# FPGA_Core.net
KiCad netlist of a schematic drawn in Altium Designer
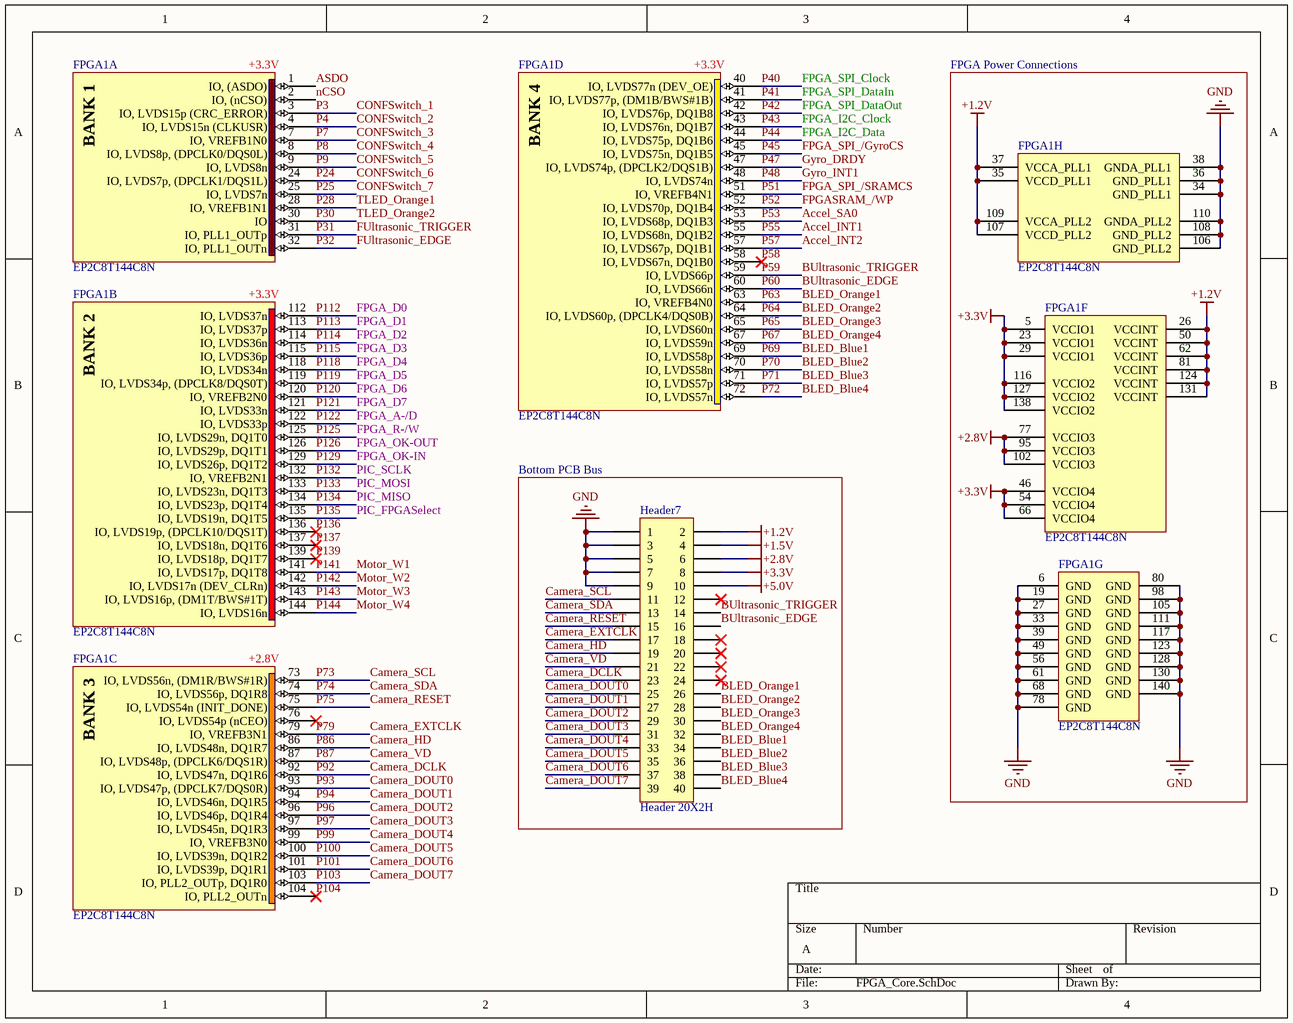
[diagram p0: FPGA_Core.SchDoc]

(export (version "E")
  (design (tool "Eeschema 10.0.6"))
  (components
    (comp (ref "FPGA1")
      (value "EP2C8T144C8N")
      (footprint "TQFP144_N")
      (fields (field (name "PUBLISHER") "Altium Limited"))
      (libsource (lib "Altera Cyclone II") (part "EP2C8T144C8N"))
    )
    (comp (ref "Header7")
      (value "Header 20X2H")
      (footprint "HDR2X20")
      (description "Header, 20-Pin, Dual row, Right Angle")
      (fields (field (name "PUBLISHER") "Altium Limited"))
      (libsource (lib "Miscellaneous Connectors") (part "Header 20X2H"))
    )
  )
  (nets
    (net (code "1") (name "+1.2V") (class "Default")
      (node (ref "FPGA1") (pin "107") (pinfunction "VCCD_PLL2_107") (pintype "power_in"))
      (node (ref "FPGA1") (pin "109") (pinfunction "VCCA_PLL2_109") (pintype "power_in"))
      (node (ref "FPGA1") (pin "124") (pinfunction "VCCINT_124") (pintype "power_in"))
      (node (ref "FPGA1") (pin "131") (pinfunction "VCCINT_131") (pintype "power_in"))
      (node (ref "FPGA1") (pin "26") (pinfunction "VCCINT_26") (pintype "power_in"))
      (node (ref "FPGA1") (pin "35") (pinfunction "VCCD_PLL1_35") (pintype "power_in"))
      (node (ref "FPGA1") (pin "37") (pinfunction "VCCA_PLL1_37") (pintype "power_in"))
      (node (ref "FPGA1") (pin "50") (pinfunction "VCCINT_50") (pintype "power_in"))
      (node (ref "FPGA1") (pin "62") (pinfunction "VCCINT_62") (pintype "power_in"))
      (node (ref "FPGA1") (pin "81") (pinfunction "VCCINT_81") (pintype "power_in"))
      (node (ref "Header7") (pin "2") (pinfunction "2_2") (pintype "passive"))
    )
    (net (code "2") (name "+1.5V") (class "Default")
      (node (ref "Header7") (pin "4") (pinfunction "4_4") (pintype "passive"))
    )
    (net (code "3") (name "+2.8V") (class "Default")
      (node (ref "FPGA1") (pin "102") (pinfunction "VCCIO3_102") (pintype "power_in"))
      (node (ref "FPGA1") (pin "77") (pinfunction "VCCIO3_77") (pintype "power_in"))
      (node (ref "FPGA1") (pin "95") (pinfunction "VCCIO3_95") (pintype "power_in"))
      (node (ref "Header7") (pin "6") (pinfunction "6_6") (pintype "passive"))
    )
    (net (code "4") (name "+3.3V") (class "Default")
      (node (ref "FPGA1") (pin "116") (pinfunction "VCCIO2_116") (pintype "power_in"))
      (node (ref "FPGA1") (pin "127") (pinfunction "VCCIO2_127") (pintype "power_in"))
      (node (ref "FPGA1") (pin "138") (pinfunction "VCCIO2_138") (pintype "power_in"))
      (node (ref "FPGA1") (pin "23") (pinfunction "VCCIO1_23") (pintype "power_in"))
      (node (ref "FPGA1") (pin "29") (pinfunction "VCCIO1_29") (pintype "power_in"))
      (node (ref "FPGA1") (pin "46") (pinfunction "VCCIO4_46") (pintype "power_in"))
      (node (ref "FPGA1") (pin "5") (pinfunction "VCCIO1_5") (pintype "power_in"))
      (node (ref "FPGA1") (pin "54") (pinfunction "VCCIO4_54") (pintype "power_in"))
      (node (ref "FPGA1") (pin "66") (pinfunction "VCCIO4_66") (pintype "power_in"))
      (node (ref "Header7") (pin "8") (pinfunction "8_8") (pintype "passive"))
    )
    (net (code "5") (name "+5.0V") (class "Default")
      (node (ref "Header7") (pin "10") (pinfunction "10_10") (pintype "passive"))
    )
    (net (code "6") (name "/ASDO") (class "Default")
      (node (ref "FPGA1") (pin "1") (pinfunction "IO,_(ASDO)_1") (pintype "bidirectional"))
    )
    (net (code "7") (name "/Accel_INT1") (class "Default")
      (node (ref "FPGA1") (pin "55") (pinfunction "IO,_LVDS68n,_DQ1B2_55") (pintype "bidirectional"))
    )
    (net (code "8") (name "/Accel_INT2") (class "Default")
      (node (ref "FPGA1") (pin "57") (pinfunction "IO,_LVDS67p,_DQ1B1_57") (pintype "bidirectional"))
    )
    (net (code "9") (name "/Accel_SA0") (class "Default")
      (node (ref "FPGA1") (pin "53") (pinfunction "IO,_LVDS68p,_DQ1B3_53") (pintype "bidirectional"))
    )
    (net (code "10") (name "/BLED_Blue1") (class "Default")
      (node (ref "FPGA1") (pin "69") (pinfunction "IO,_LVDS58p_69") (pintype "bidirectional"))
      (node (ref "Header7") (pin "34") (pinfunction "34_34") (pintype "passive"))
    )
    (net (code "11") (name "/BLED_Blue2") (class "Default")
      (node (ref "FPGA1") (pin "70") (pinfunction "IO,_LVDS58n_70") (pintype "bidirectional"))
      (node (ref "Header7") (pin "36") (pinfunction "36_36") (pintype "passive"))
    )
    (net (code "12") (name "/BLED_Blue3") (class "Default")
      (node (ref "FPGA1") (pin "71") (pinfunction "IO,_LVDS57p_71") (pintype "bidirectional"))
      (node (ref "Header7") (pin "38") (pinfunction "38_38") (pintype "passive"))
    )
    (net (code "13") (name "/BLED_Blue4") (class "Default")
      (node (ref "FPGA1") (pin "72") (pinfunction "IO,_LVDS57n_72") (pintype "bidirectional"))
      (node (ref "Header7") (pin "40") (pinfunction "40_40") (pintype "passive"))
    )
    (net (code "14") (name "/BLED_Orange1") (class "Default")
      (node (ref "FPGA1") (pin "63") (pinfunction "IO,_VREFB4N0_63") (pintype "bidirectional"))
      (node (ref "Header7") (pin "26") (pinfunction "26_26") (pintype "passive"))
    )
    (net (code "15") (name "/BLED_Orange2") (class "Default")
      (node (ref "FPGA1") (pin "64") (pinfunction "IO,_LVDS60p,_(DPCLK4/DQS0B)_64") (pintype "bidirectional"))
      (node (ref "Header7") (pin "28") (pinfunction "28_28") (pintype "passive"))
    )
    (net (code "16") (name "/BLED_Orange3") (class "Default")
      (node (ref "FPGA1") (pin "65") (pinfunction "IO,_LVDS60n_65") (pintype "bidirectional"))
      (node (ref "Header7") (pin "30") (pinfunction "30_30") (pintype "passive"))
    )
    (net (code "17") (name "/BLED_Orange4") (class "Default")
      (node (ref "FPGA1") (pin "67") (pinfunction "IO,_LVDS59n_67") (pintype "bidirectional"))
      (node (ref "Header7") (pin "32") (pinfunction "32_32") (pintype "passive"))
    )
    (net (code "18") (name "/BUltrasonic_EDGE") (class "Default")
      (node (ref "FPGA1") (pin "60") (pinfunction "IO,_LVDS66n_60") (pintype "bidirectional"))
      (node (ref "Header7") (pin "16") (pinfunction "16_16") (pintype "passive"))
    )
    (net (code "19") (name "/BUltrasonic_TRIGGER") (class "Default")
      (node (ref "FPGA1") (pin "59") (pinfunction "IO,_LVDS66p_59") (pintype "bidirectional"))
      (node (ref "Header7") (pin "14") (pinfunction "14_14") (pintype "passive"))
    )
    (net (code "20") (name "/CONFSwitch_1") (class "Default")
      (node (ref "FPGA1") (pin "3") (pinfunction "IO,_LVDS15p_(CRC_ERROR)_3") (pintype "bidirectional"))
    )
    (net (code "21") (name "/CONFSwitch_2") (class "Default")
      (node (ref "FPGA1") (pin "4") (pinfunction "IO,_LVDS15n_(CLKUSR)_4") (pintype "bidirectional"))
    )
    (net (code "22") (name "/CONFSwitch_3") (class "Default")
      (node (ref "FPGA1") (pin "7") (pinfunction "IO,_VREFB1N0_7") (pintype "bidirectional"))
    )
    (net (code "23") (name "/CONFSwitch_4") (class "Default")
      (node (ref "FPGA1") (pin "8") (pinfunction "IO,_LVDS8p,_(DPCLK0/DQS0L)_8") (pintype "bidirectional"))
    )
    (net (code "24") (name "/CONFSwitch_5") (class "Default")
      (node (ref "FPGA1") (pin "9") (pinfunction "IO,_LVDS8n_9") (pintype "bidirectional"))
    )
    (net (code "25") (name "/CONFSwitch_6") (class "Default")
      (node (ref "FPGA1") (pin "24") (pinfunction "IO,_LVDS7p,_(DPCLK1/DQS1L)_24") (pintype "bidirectional"))
    )
    (net (code "26") (name "/CONFSwitch_7") (class "Default")
      (node (ref "FPGA1") (pin "25") (pinfunction "IO,_LVDS7n_25") (pintype "bidirectional"))
    )
    (net (code "27") (name "/Camera_DCLK") (class "Default")
      (node (ref "FPGA1") (pin "92") (pinfunction "IO,_LVDS47n,_DQ1R6_92") (pintype "bidirectional"))
      (node (ref "Header7") (pin "23") (pinfunction "23_23") (pintype "passive"))
    )
    (net (code "28") (name "/Camera_DOUT0") (class "Default")
      (node (ref "FPGA1") (pin "93") (pinfunction "IO,_LVDS47p,_(DPCLK7/DQS0R)_93") (pintype "bidirectional"))
      (node (ref "Header7") (pin "25") (pinfunction "25_25") (pintype "passive"))
    )
    (net (code "29") (name "/Camera_DOUT1") (class "Default")
      (node (ref "FPGA1") (pin "94") (pinfunction "IO,_LVDS46n,_DQ1R5_94") (pintype "bidirectional"))
      (node (ref "Header7") (pin "27") (pinfunction "27_27") (pintype "passive"))
    )
    (net (code "30") (name "/Camera_DOUT2") (class "Default")
      (node (ref "FPGA1") (pin "96") (pinfunction "IO,_LVDS46p,_DQ1R4_96") (pintype "bidirectional"))
      (node (ref "Header7") (pin "29") (pinfunction "29_29") (pintype "passive"))
    )
    (net (code "31") (name "/Camera_DOUT3") (class "Default")
      (node (ref "FPGA1") (pin "97") (pinfunction "IO,_LVDS45n,_DQ1R3_97") (pintype "bidirectional"))
      (node (ref "Header7") (pin "31") (pinfunction "31_31") (pintype "passive"))
    )
    (net (code "32") (name "/Camera_DOUT4") (class "Default")
      (node (ref "FPGA1") (pin "99") (pinfunction "IO,_VREFB3N0_99") (pintype "bidirectional"))
      (node (ref "Header7") (pin "33") (pinfunction "33_33") (pintype "passive"))
    )
    (net (code "33") (name "/Camera_DOUT5") (class "Default")
      (node (ref "FPGA1") (pin "100") (pinfunction "IO,_LVDS39n,_DQ1R2_100") (pintype "bidirectional"))
      (node (ref "Header7") (pin "35") (pinfunction "35_35") (pintype "passive"))
    )
    (net (code "34") (name "/Camera_DOUT6") (class "Default")
      (node (ref "FPGA1") (pin "101") (pinfunction "IO,_LVDS39p,_DQ1R1_101") (pintype "bidirectional"))
      (node (ref "Header7") (pin "37") (pinfunction "37_37") (pintype "passive"))
    )
    (net (code "35") (name "/Camera_DOUT7") (class "Default")
      (node (ref "FPGA1") (pin "103") (pinfunction "IO,_PLL2_OUTp,_DQ1R0_103") (pintype "bidirectional"))
      (node (ref "Header7") (pin "39") (pinfunction "39_39") (pintype "passive"))
    )
    (net (code "36") (name "/Camera_EXTCLK") (class "Default")
      (node (ref "FPGA1") (pin "79") (pinfunction "IO,_VREFB3N1_79") (pintype "bidirectional"))
      (node (ref "Header7") (pin "17") (pinfunction "17_17") (pintype "passive"))
    )
    (net (code "37") (name "/Camera_HD") (class "Default")
      (node (ref "FPGA1") (pin "86") (pinfunction "IO,_LVDS48n,_DQ1R7_86") (pintype "bidirectional"))
      (node (ref "Header7") (pin "19") (pinfunction "19_19") (pintype "passive"))
    )
    (net (code "38") (name "/Camera_RESET") (class "Default")
      (node (ref "FPGA1") (pin "75") (pinfunction "IO,_LVDS54n_(INIT_DONE)_75") (pintype "bidirectional"))
      (node (ref "Header7") (pin "15") (pinfunction "15_15") (pintype "passive"))
    )
    (net (code "39") (name "/Camera_SCL") (class "Default")
      (node (ref "FPGA1") (pin "73") (pinfunction "IO,_LVDS56n,_(DM1R/BWS#1R)_73") (pintype "bidirectional"))
      (node (ref "Header7") (pin "11") (pinfunction "11_11") (pintype "passive"))
    )
    (net (code "40") (name "/Camera_SDA") (class "Default")
      (node (ref "FPGA1") (pin "74") (pinfunction "IO,_LVDS56p,_DQ1R8_74") (pintype "bidirectional"))
      (node (ref "Header7") (pin "13") (pinfunction "13_13") (pintype "passive"))
    )
    (net (code "41") (name "/Camera_VD") (class "Default")
      (node (ref "FPGA1") (pin "87") (pinfunction "IO,_LVDS48p,_(DPCLK6/DQS1R)_87") (pintype "bidirectional"))
      (node (ref "Header7") (pin "21") (pinfunction "21_21") (pintype "passive"))
    )
    (net (code "42") (name "/FPGASRAM_{slash}WP") (class "Default")
      (node (ref "FPGA1") (pin "52") (pinfunction "IO,_LVDS70p,_DQ1B4_52") (pintype "bidirectional"))
    )
    (net (code "43") (name "/FPGA_A-{slash}D") (class "Default")
      (node (ref "FPGA1") (pin "122") (pinfunction "IO,_LVDS33p_122") (pintype "bidirectional"))
    )
    (net (code "44") (name "/FPGA_D0") (class "Default")
      (node (ref "FPGA1") (pin "112") (pinfunction "IO,_LVDS37n_112") (pintype "bidirectional"))
    )
    (net (code "45") (name "/FPGA_D1") (class "Default")
      (node (ref "FPGA1") (pin "113") (pinfunction "IO,_LVDS37p_113") (pintype "bidirectional"))
    )
    (net (code "46") (name "/FPGA_D2") (class "Default")
      (node (ref "FPGA1") (pin "114") (pinfunction "IO,_LVDS36n_114") (pintype "bidirectional"))
    )
    (net (code "47") (name "/FPGA_D3") (class "Default")
      (node (ref "FPGA1") (pin "115") (pinfunction "IO,_LVDS36p_115") (pintype "bidirectional"))
    )
    (net (code "48") (name "/FPGA_D4") (class "Default")
      (node (ref "FPGA1") (pin "118") (pinfunction "IO,_LVDS34n_118") (pintype "bidirectional"))
    )
    (net (code "49") (name "/FPGA_D5") (class "Default")
      (node (ref "FPGA1") (pin "119") (pinfunction "IO,_LVDS34p,_(DPCLK8/DQS0T)_119") (pintype "bidirectional"))
    )
    (net (code "50") (name "/FPGA_D6") (class "Default")
      (node (ref "FPGA1") (pin "120") (pinfunction "IO,_VREFB2N0_120") (pintype "bidirectional"))
    )
    (net (code "51") (name "/FPGA_D7") (class "Default")
      (node (ref "FPGA1") (pin "121") (pinfunction "IO,_LVDS33n_121") (pintype "bidirectional"))
    )
    (net (code "52") (name "/FPGA_I2C_Clock") (class "Default")
      (node (ref "FPGA1") (pin "43") (pinfunction "IO,_LVDS76n,_DQ1B7_43") (pintype "bidirectional"))
    )
    (net (code "53") (name "/FPGA_I2C_Data") (class "Default")
      (node (ref "FPGA1") (pin "44") (pinfunction "IO,_LVDS75p,_DQ1B6_44") (pintype "bidirectional"))
    )
    (net (code "54") (name "/FPGA_OK-IN") (class "Default")
      (node (ref "FPGA1") (pin "129") (pinfunction "IO,_LVDS26p,_DQ1T2_129") (pintype "bidirectional"))
    )
    (net (code "55") (name "/FPGA_OK-OUT") (class "Default")
      (node (ref "FPGA1") (pin "126") (pinfunction "IO,_LVDS29p,_DQ1T1_126") (pintype "bidirectional"))
    )
    (net (code "56") (name "/FPGA_R-{slash}W") (class "Default")
      (node (ref "FPGA1") (pin "125") (pinfunction "IO,_LVDS29n,_DQ1T0_125") (pintype "bidirectional"))
    )
    (net (code "57") (name "/FPGA_SPI_Clock") (class "Default")
      (node (ref "FPGA1") (pin "40") (pinfunction "IO,_LVDS77n_(DEV_OE)_40") (pintype "bidirectional"))
    )
    (net (code "58") (name "/FPGA_SPI_DataIn") (class "Default")
      (node (ref "FPGA1") (pin "41") (pinfunction "IO,_LVDS77p,_(DM1B/BWS#1B)_41") (pintype "bidirectional"))
    )
    (net (code "59") (name "/FPGA_SPI_DataOut") (class "Default")
      (node (ref "FPGA1") (pin "42") (pinfunction "IO,_LVDS76p,_DQ1B8_42") (pintype "bidirectional"))
    )
    (net (code "60") (name "/FPGA_SPI_{slash}GyroCS") (class "Default")
      (node (ref "FPGA1") (pin "45") (pinfunction "IO,_LVDS75n,_DQ1B5_45") (pintype "bidirectional"))
    )
    (net (code "61") (name "/FPGA_SPI_{slash}SRAMCS") (class "Default")
      (node (ref "FPGA1") (pin "51") (pinfunction "IO,_VREFB4N1_51") (pintype "bidirectional"))
    )
    (net (code "62") (name "/FUltrasonic_EDGE") (class "Default")
      (node (ref "FPGA1") (pin "32") (pinfunction "IO,_PLL1_OUTn_32") (pintype "bidirectional"))
    )
    (net (code "63") (name "/FUltrasonic_TRIGGER") (class "Default")
      (node (ref "FPGA1") (pin "31") (pinfunction "IO,_PLL1_OUTp_31") (pintype "bidirectional"))
    )
    (net (code "64") (name "/Gyro_DRDY") (class "Default")
      (node (ref "FPGA1") (pin "47") (pinfunction "IO,_LVDS74p,_(DPCLK2/DQS1B)_47") (pintype "bidirectional"))
    )
    (net (code "65") (name "/Gyro_INT1") (class "Default")
      (node (ref "FPGA1") (pin "48") (pinfunction "IO,_LVDS74n_48") (pintype "bidirectional"))
    )
    (net (code "66") (name "/Motor_W1") (class "Default")
      (node (ref "FPGA1") (pin "141") (pinfunction "IO,_LVDS17p,_DQ1T8_141") (pintype "bidirectional"))
    )
    (net (code "67") (name "/Motor_W2") (class "Default")
      (node (ref "FPGA1") (pin "142") (pinfunction "IO,_LVDS17n_(DEV_CLRn)_142") (pintype "bidirectional"))
    )
    (net (code "68") (name "/Motor_W3") (class "Default")
      (node (ref "FPGA1") (pin "143") (pinfunction "IO,_LVDS16p,_(DM1T/BWS#1T)_143") (pintype "bidirectional"))
    )
    (net (code "69") (name "/Motor_W4") (class "Default")
      (node (ref "FPGA1") (pin "144") (pinfunction "IO,_LVDS16n_144") (pintype "bidirectional"))
    )
    (net (code "70") (name "/P28") (class "Default")
      (node (ref "FPGA1") (pin "28") (pinfunction "IO,_VREFB1N1_28") (pintype "bidirectional"))
    )
    (net (code "71") (name "/P30") (class "Default")
      (node (ref "FPGA1") (pin "30") (pinfunction "IO_30") (pintype "bidirectional"))
    )
    (net (code "72") (name "/P58") (class "Default")
      (node (ref "FPGA1") (pin "58") (pinfunction "IO,_LVDS67n,_DQ1B0_58") (pintype "bidirectional+no_connect"))
    )
    (net (code "73") (name "/P104") (class "Default")
      (node (ref "FPGA1") (pin "104") (pinfunction "IO,_PLL2_OUTn_104") (pintype "bidirectional+no_connect"))
    )
    (net (code "74") (name "/P132") (class "Default")
      (node (ref "FPGA1") (pin "132") (pinfunction "IO,_VREFB2N1_132") (pintype "bidirectional"))
    )
    (net (code "75") (name "/P133") (class "Default")
      (node (ref "FPGA1") (pin "133") (pinfunction "IO,_LVDS23n,_DQ1T3_133") (pintype "bidirectional"))
    )
    (net (code "76") (name "/P134") (class "Default")
      (node (ref "FPGA1") (pin "134") (pinfunction "IO,_LVDS23p,_DQ1T4_134") (pintype "bidirectional"))
    )
    (net (code "77") (name "/P135") (class "Default")
      (node (ref "FPGA1") (pin "135") (pinfunction "IO,_LVDS19n,_DQ1T5_135") (pintype "bidirectional"))
    )
    (net (code "78") (name "/P136") (class "Default")
      (node (ref "FPGA1") (pin "136") (pinfunction "IO,_LVDS19p,_(DPCLK10/DQS1T)_136") (pintype "bidirectional+no_connect"))
    )
    (net (code "79") (name "/P137") (class "Default")
      (node (ref "FPGA1") (pin "137") (pinfunction "IO,_LVDS18n,_DQ1T6_137") (pintype "bidirectional+no_connect"))
    )
    (net (code "80") (name "/P139") (class "Default")
      (node (ref "FPGA1") (pin "139") (pinfunction "IO,_LVDS18p,_DQ1T7_139") (pintype "bidirectional+no_connect"))
    )
    (net (code "81") (name "/nCSO") (class "Default")
      (node (ref "FPGA1") (pin "2") (pinfunction "IO,_(nCSO)_2") (pintype "bidirectional"))
    )
    (net (code "82") (name "GND") (class "Default")
      (node (ref "FPGA1") (pin "105") (pinfunction "GND_105") (pintype "power_in"))
      (node (ref "FPGA1") (pin "106") (pinfunction "GND_PLL2_106") (pintype "power_in"))
      (node (ref "FPGA1") (pin "108") (pinfunction "GND_PLL2_108") (pintype "power_in"))
      (node (ref "FPGA1") (pin "110") (pinfunction "GNDA_PLL2_110") (pintype "power_in"))
      (node (ref "FPGA1") (pin "111") (pinfunction "GND_111") (pintype "power_in"))
      (node (ref "FPGA1") (pin "117") (pinfunction "GND_117") (pintype "power_in"))
      (node (ref "FPGA1") (pin "123") (pinfunction "GND_123") (pintype "power_in"))
      (node (ref "FPGA1") (pin "128") (pinfunction "GND_128") (pintype "power_in"))
      (node (ref "FPGA1") (pin "130") (pinfunction "GND_130") (pintype "power_in"))
      (node (ref "FPGA1") (pin "140") (pinfunction "GND_140") (pintype "power_in"))
      (node (ref "FPGA1") (pin "19") (pinfunction "GND_19") (pintype "power_in"))
      (node (ref "FPGA1") (pin "27") (pinfunction "GND_27") (pintype "power_in"))
      (node (ref "FPGA1") (pin "33") (pinfunction "GND_33") (pintype "power_in"))
      (node (ref "FPGA1") (pin "34") (pinfunction "GND_PLL1_34") (pintype "power_in"))
      (node (ref "FPGA1") (pin "36") (pinfunction "GND_PLL1_36") (pintype "power_in"))
      (node (ref "FPGA1") (pin "38") (pinfunction "GNDA_PLL1_38") (pintype "power_in"))
      (node (ref "FPGA1") (pin "39") (pinfunction "GND_39") (pintype "power_in"))
      (node (ref "FPGA1") (pin "49") (pinfunction "GND_49") (pintype "power_in"))
      (node (ref "FPGA1") (pin "56") (pinfunction "GND_56") (pintype "power_in"))
      (node (ref "FPGA1") (pin "6") (pinfunction "GND_6") (pintype "power_in"))
      (node (ref "FPGA1") (pin "61") (pinfunction "GND_61") (pintype "power_in"))
      (node (ref "FPGA1") (pin "68") (pinfunction "GND_68") (pintype "power_in"))
      (node (ref "FPGA1") (pin "78") (pinfunction "GND_78") (pintype "power_in"))
      (node (ref "FPGA1") (pin "80") (pinfunction "GND_80") (pintype "power_in"))
      (node (ref "FPGA1") (pin "98") (pinfunction "GND_98") (pintype "power_in"))
      (node (ref "Header7") (pin "1") (pinfunction "1_1") (pintype "passive"))
      (node (ref "Header7") (pin "3") (pinfunction "3_3") (pintype "passive"))
      (node (ref "Header7") (pin "5") (pinfunction "5_5") (pintype "passive"))
      (node (ref "Header7") (pin "7") (pinfunction "7_7") (pintype "passive"))
      (node (ref "Header7") (pin "9") (pinfunction "9_9") (pintype "passive"))
    )
    (net (code "83") (name "unconnected-(FPGA1C-IO,_LVDS54p_(nCEO)-Pad76)") (class "Default")
      (node (ref "FPGA1") (pin "76") (pinfunction "IO,_LVDS54p_(nCEO)_76") (pintype "bidirectional+no_connect"))
    )
    (net (code "84") (name "unconnected-(Header7-Pad12)") (class "Default")
      (node (ref "Header7") (pin "12") (pinfunction "12_12") (pintype "passive+no_connect"))
    )
    (net (code "85") (name "unconnected-(Header7-Pad18)") (class "Default")
      (node (ref "Header7") (pin "18") (pinfunction "18_18") (pintype "passive+no_connect"))
    )
    (net (code "86") (name "unconnected-(Header7-Pad20)") (class "Default")
      (node (ref "Header7") (pin "20") (pinfunction "20_20") (pintype "passive+no_connect"))
    )
    (net (code "87") (name "unconnected-(Header7-Pad22)") (class "Default")
      (node (ref "Header7") (pin "22") (pinfunction "22_22") (pintype "passive+no_connect"))
    )
    (net (code "88") (name "unconnected-(Header7-Pad24)") (class "Default")
      (node (ref "Header7") (pin "24") (pinfunction "24_24") (pintype "passive+no_connect"))
    )
  )
)
